# br44.net
KiCad netlist of a schematic drawn in EAGLE
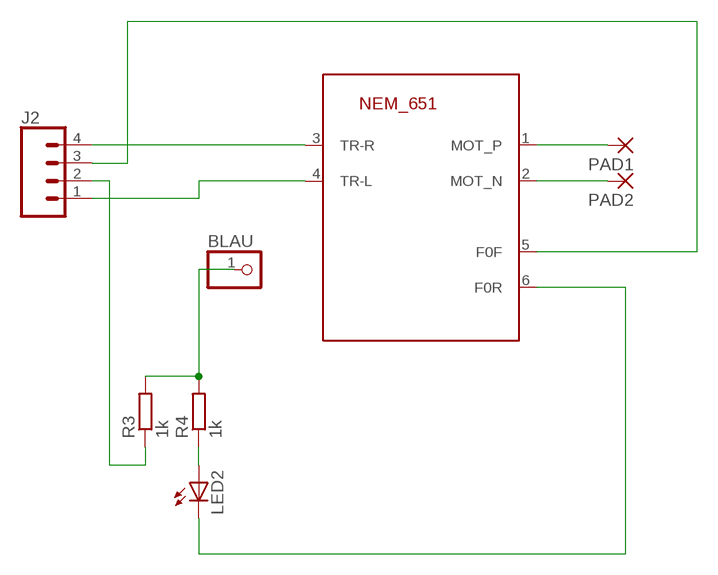
[diagram p0: schematic, sheet 1]

(export (version "E")
  (design (tool "Eeschema 10.0.6"))
  (components
    (comp (ref "BLAU")
      (value "PINHD-1X1")
      (footprint "eagle-import:1X01")
      (libsource (lib "eagle-import") (part "PINHD-1X1"))
    )
    (comp (ref "J2")
      (value "CONN_041X04_NO_SILK")
      (footprint "eagle-import:1X04_NO_SILK")
      (libsource (lib "eagle-import") (part "CONN_041X04_NO_SILK"))
    )
    (comp (ref "LED2")
      (value "LED3MM")
      (footprint "eagle-import:LED3MM")
      (libsource (lib "eagle-import") (part "LED3MM"))
    )
    (comp (ref "PAD1")
      (value "SMD5")
      (footprint "eagle-import:SMD2,54-5,08")
      (libsource (lib "eagle-import") (part "SMD5"))
    )
    (comp (ref "PAD2")
      (value "SMD5")
      (footprint "eagle-import:SMD2,54-5,08")
      (libsource (lib "eagle-import") (part "SMD5"))
    )
    (comp (ref "R3")
      (value "1k")
      (footprint "eagle-import:0204V")
      (libsource (lib "eagle-import") (part "R-EU_0204/2V"))
    )
    (comp (ref "R4")
      (value "1k")
      (footprint "eagle-import:0204V")
      (libsource (lib "eagle-import") (part "R-EU_0204/2V"))
    )
    (comp (ref "U$1")
      (value "NEM_651-TS")
      (footprint "eagle-import:53047-06")
      (libsource (lib "eagle-import") (part "NEM_651-TS"))
    )
  )
  (nets
    (net (code "1") (name "Net-(BLAU-Pad1)") (class "Default")
      (node (ref "BLAU") (pin "1") (pinfunction "1_1") (pintype "passive"))
      (node (ref "R3") (pin "2") (pinfunction "2_2") (pintype "passive"))
      (node (ref "R4") (pin "2") (pinfunction "2_2") (pintype "passive"))
    )
    (net (code "2") (name "Net-(J2-Pad2)") (class "Default")
      (node (ref "J2") (pin "2") (pinfunction "2_2") (pintype "passive"))
      (node (ref "R3") (pin "1") (pinfunction "1_1") (pintype "passive"))
    )
    (net (code "3") (name "Net-(LED2-C)") (class "Default")
      (node (ref "LED2") (pin "K") (pinfunction "C_K") (pintype "passive"))
      (node (ref "U$1") (pin "6") (pinfunction "F0R_6") (pintype "bidirectional"))
    )
    (net (code "4") (name "Net-(LED2-PadA)") (class "Default")
      (node (ref "LED2") (pin "A") (pinfunction "A_A") (pintype "passive"))
      (node (ref "R4") (pin "1") (pinfunction "1_1") (pintype "passive"))
    )
    (net (code "5") (name "Net-(PAD1-P)") (class "Default")
      (node (ref "PAD1") (pin "1") (pinfunction "P_1") (pintype "passive"))
      (node (ref "U$1") (pin "1") (pinfunction "MOT_P_1") (pintype "bidirectional"))
    )
    (net (code "6") (name "Net-(PAD2-P)") (class "Default")
      (node (ref "PAD2") (pin "1") (pinfunction "P_1") (pintype "passive"))
      (node (ref "U$1") (pin "2") (pinfunction "MOT_N_2") (pintype "bidirectional"))
    )
    (net (code "7") (name "Net-(U$1-F0F)") (class "Default")
      (node (ref "J2") (pin "3") (pinfunction "3_3") (pintype "passive"))
      (node (ref "U$1") (pin "5") (pinfunction "F0F_5") (pintype "bidirectional"))
    )
    (net (code "8") (name "Net-(U$1-TR-L)") (class "Default")
      (node (ref "J2") (pin "1") (pinfunction "1_1") (pintype "passive"))
      (node (ref "U$1") (pin "4") (pinfunction "TR-L_4") (pintype "bidirectional"))
    )
    (net (code "9") (name "Net-(U$1-TR-R)") (class "Default")
      (node (ref "J2") (pin "4") (pinfunction "4_4") (pintype "passive"))
      (node (ref "U$1") (pin "3") (pinfunction "TR-R_3") (pintype "bidirectional"))
    )
  )
)
